# ECG_V3.net
KiCad netlist of a schematic drawn in EAGLE
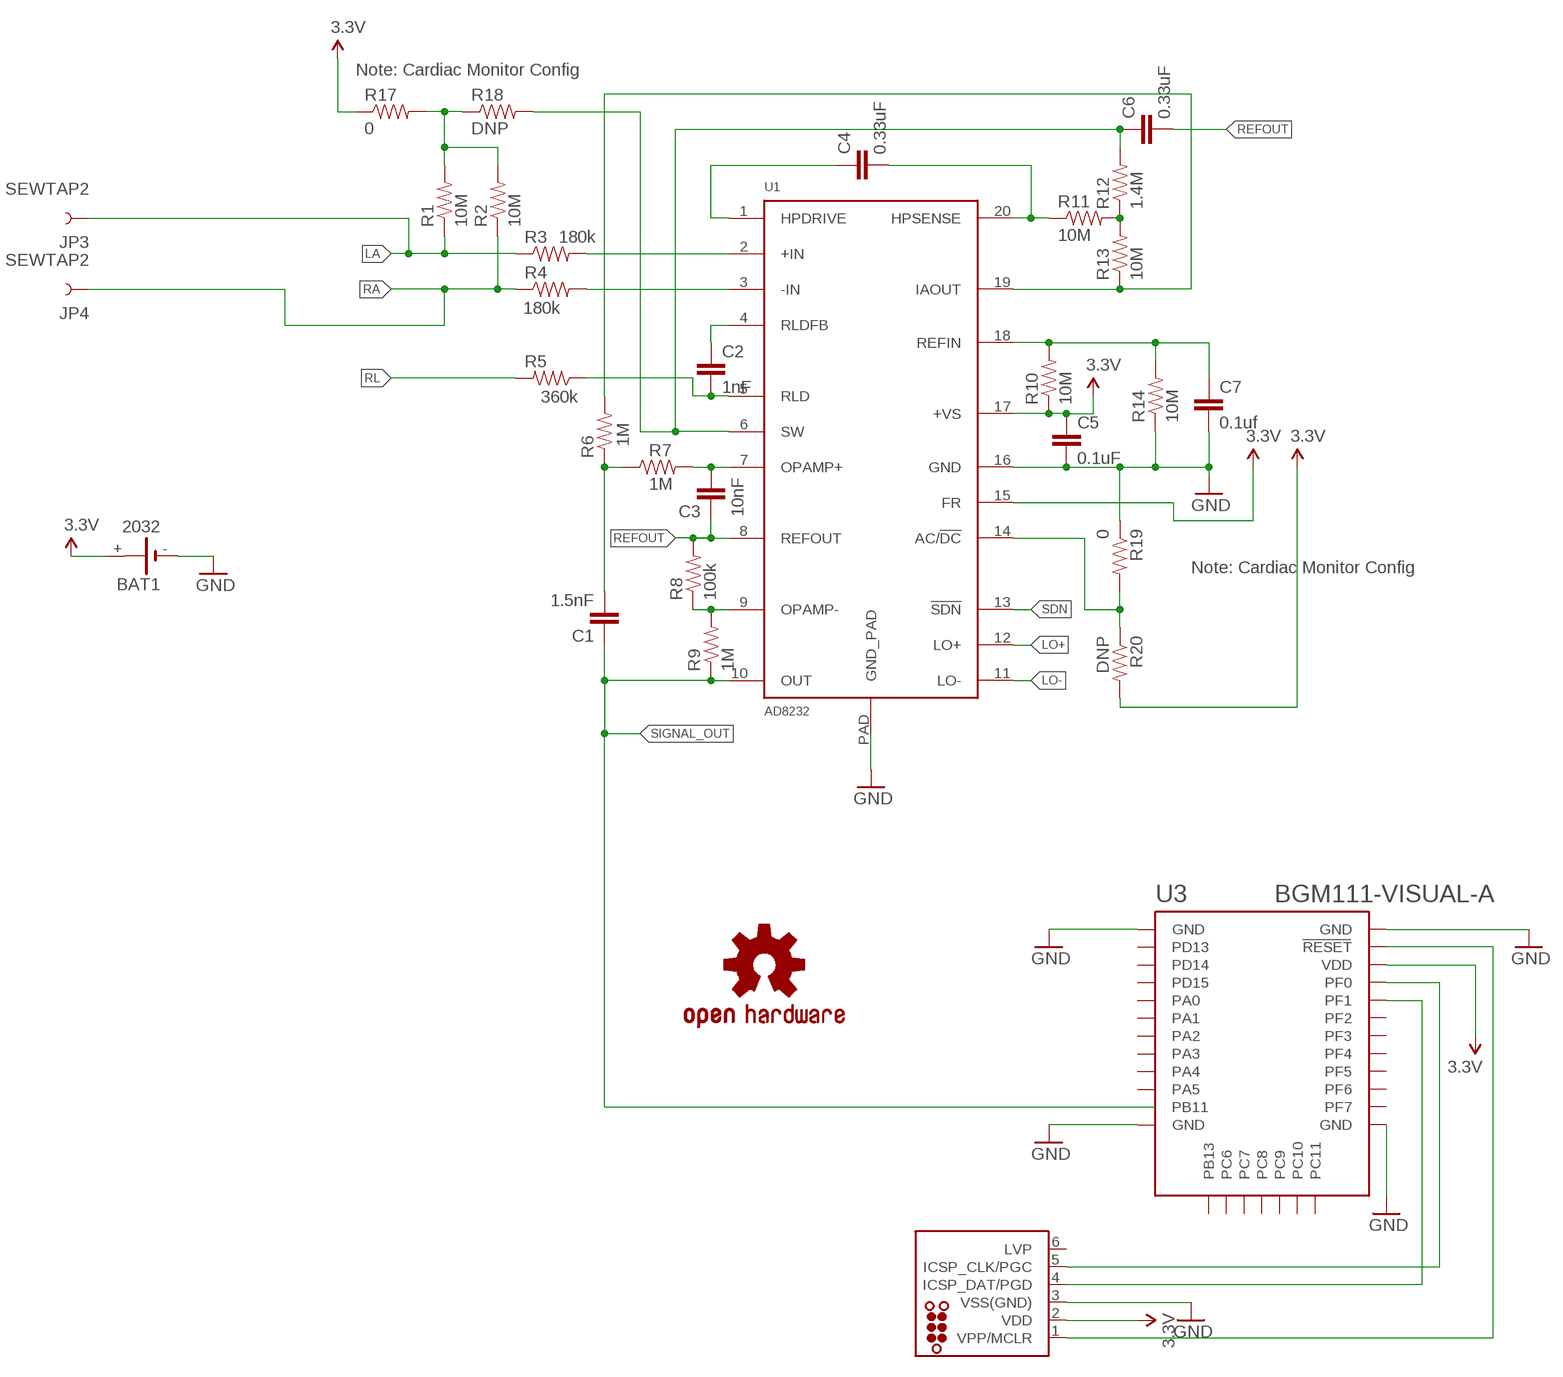
[diagram p0: schematic, sheet 1]

(export (version "E")
  (design (tool "Eeschema 10.0.6"))
  (components
    (comp (ref "BAT1")
      (value "2032")
      (footprint "eagle-import:KZH20SMD")
      (libsource (lib "eagle-import") (part "2032"))
    )
    (comp (ref "C1")
      (value "1.5nF")
      (footprint "eagle-import:0603-CAP")
      (libsource (lib "eagle-import") (part "CAP0603-CAP"))
    )
    (comp (ref "C2")
      (value "1nF")
      (footprint "eagle-import:0603-CAP")
      (libsource (lib "eagle-import") (part "CAP0603-CAP"))
    )
    (comp (ref "C3")
      (value "10nF")
      (footprint "eagle-import:0603-CAP")
      (libsource (lib "eagle-import") (part "CAP0603-CAP"))
    )
    (comp (ref "C4")
      (value "0.33uF")
      (footprint "eagle-import:0805")
      (libsource (lib "eagle-import") (part "CAP0805"))
    )
    (comp (ref "C5")
      (value "0.1uF")
      (footprint "eagle-import:0603-CAP")
      (libsource (lib "eagle-import") (part "CAP0603-CAP"))
    )
    (comp (ref "C6")
      (value "0.33uF")
      (footprint "eagle-import:0805")
      (libsource (lib "eagle-import") (part "CAP0805"))
    )
    (comp (ref "C7")
      (value "0.1uf")
      (footprint "eagle-import:0603-CAP")
      (libsource (lib "eagle-import") (part "CAP0603-CAP"))
    )
    (comp (ref "J2")
      (value "TC2030-MCP-NL")
      (footprint "eagle-import:TC2030-MCP-NL")
      (libsource (lib "eagle-import") (part "TC2030-MCP-NL"))
    )
    (comp (ref "JP3")
      (value "SEWTAP2")
      (footprint "eagle-import:PETAL-LONG-2")
      (libsource (lib "eagle-import") (part "SEWTAP2"))
    )
    (comp (ref "JP4")
      (value "SEWTAP2")
      (footprint "eagle-import:PETAL-LONG-2")
      (libsource (lib "eagle-import") (part "SEWTAP2"))
    )
    (comp (ref "LOGO1")
      (value "OSHW-LOGOS")
      (footprint "eagle-import:OSHW-LOGO-S")
      (libsource (lib "eagle-import") (part "OSHW-LOGOS"))
    )
    (comp (ref "R1")
      (value "10M")
      (footprint "eagle-import:0603-RES")
      (libsource (lib "eagle-import") (part "RESISTOR0603-RES"))
    )
    (comp (ref "R2")
      (value "10M")
      (footprint "eagle-import:0603-RES")
      (libsource (lib "eagle-import") (part "RESISTOR0603-RES"))
    )
    (comp (ref "R3")
      (value "180k")
      (footprint "eagle-import:0603-RES")
      (libsource (lib "eagle-import") (part "RESISTOR0603-RES"))
    )
    (comp (ref "R4")
      (value "180k")
      (footprint "eagle-import:0603-RES")
      (libsource (lib "eagle-import") (part "RESISTOR0603-RES"))
    )
    (comp (ref "R5")
      (value "360k")
      (footprint "eagle-import:0603-RES")
      (libsource (lib "eagle-import") (part "RESISTOR0603-RES"))
    )
    (comp (ref "R6")
      (value "1M")
      (footprint "eagle-import:0603-RES")
      (libsource (lib "eagle-import") (part "RESISTOR0603-RES"))
    )
    (comp (ref "R7")
      (value "1M")
      (footprint "eagle-import:0603-RES")
      (libsource (lib "eagle-import") (part "RESISTOR0603-RES"))
    )
    (comp (ref "R8")
      (value "100k")
      (footprint "eagle-import:0603-RES")
      (libsource (lib "eagle-import") (part "RESISTOR0603-RES"))
    )
    (comp (ref "R9")
      (value "1M")
      (footprint "eagle-import:0603-RES")
      (libsource (lib "eagle-import") (part "RESISTOR0603-RES"))
    )
    (comp (ref "R10")
      (value "10M")
      (footprint "eagle-import:0603-RES")
      (libsource (lib "eagle-import") (part "RESISTOR0603-RES"))
    )
    (comp (ref "R11")
      (value "10M")
      (footprint "eagle-import:0603-RES")
      (libsource (lib "eagle-import") (part "RESISTOR0603-RES"))
    )
    (comp (ref "R12")
      (value "1.4M")
      (footprint "eagle-import:0603-RES")
      (libsource (lib "eagle-import") (part "RESISTOR0603-RES"))
    )
    (comp (ref "R13")
      (value "10M")
      (footprint "eagle-import:0603-RES")
      (libsource (lib "eagle-import") (part "RESISTOR0603-RES"))
    )
    (comp (ref "R14")
      (value "10M")
      (footprint "eagle-import:0603-RES")
      (libsource (lib "eagle-import") (part "RESISTOR0603-RES"))
    )
    (comp (ref "R17")
      (value "0")
      (footprint "eagle-import:0603")
      (libsource (lib "eagle-import") (part "0OHM1/10W5%(0603)"))
    )
    (comp (ref "R18")
      (value "DNP")
      (footprint "eagle-import:0603")
      (libsource (lib "eagle-import") (part "0OHM1/10W5%(0603)"))
    )
    (comp (ref "R19")
      (value "0")
      (footprint "eagle-import:0603")
      (libsource (lib "eagle-import") (part "0OHM1/10W5%(0603)"))
    )
    (comp (ref "R20")
      (value "DNP")
      (footprint "eagle-import:0603")
      (libsource (lib "eagle-import") (part "0OHM1/10W5%(0603)"))
    )
    (comp (ref "U1")
      (value "AD8232")
      (footprint "eagle-import:LFCSP_20")
      (libsource (lib "eagle-import") (part "AD8232"))
    )
    (comp (ref "U3")
      (value "BGM111-VISUAL-A")
      (footprint "eagle-import:BGM111-A")
      (libsource (lib "eagle-import") (part "BGM111-VISUAL-A"))
    )
  )
  (nets
    (net (code "1") (name "3.3V") (class "Default")
      (node (ref "BAT1") (pin "+") (pinfunction "+_+") (pintype "passive"))
      (node (ref "C5") (pin "1") (pinfunction "1_1") (pintype "passive"))
      (node (ref "J2") (pin "2") (pinfunction "VDD_2") (pintype "power_in"))
      (node (ref "R10") (pin "1") (pinfunction "1_1") (pintype "passive"))
      (node (ref "R17") (pin "1") (pinfunction "1_1") (pintype "passive"))
      (node (ref "R20") (pin "2") (pinfunction "2_2") (pintype "passive"))
      (node (ref "U1") (pin "15") (pinfunction "FR_15") (pintype "bidirectional"))
      (node (ref "U1") (pin "17") (pinfunction "+VS_17") (pintype "bidirectional"))
      (node (ref "U3") (pin "VDD") (pinfunction "VDD_VDD") (pintype "power_in"))
    )
    (net (code "2") (name "GND") (class "Default")
      (node (ref "BAT1") (pin "-") (pinfunction "-_-") (pintype "passive"))
      (node (ref "C5") (pin "2") (pinfunction "2_2") (pintype "passive"))
      (node (ref "C7") (pin "2") (pinfunction "2_2") (pintype "passive"))
      (node (ref "J2") (pin "3") (pinfunction "VSS(GND)_3") (pintype "power_in"))
      (node (ref "R14") (pin "1") (pinfunction "1_1") (pintype "passive"))
      (node (ref "R19") (pin "1") (pinfunction "1_1") (pintype "passive"))
      (node (ref "U1") (pin "16") (pinfunction "GND_16") (pintype "bidirectional"))
      (node (ref "U1") (pin "PAD") (pinfunction "GND_PAD_PAD") (pintype "bidirectional"))
      (node (ref "U3") (pin "GND") (pinfunction "GND_GND") (pintype "power_in"))
      (node (ref "U3") (pin "GND@2") (pinfunction "GND_GND@2") (pintype "power_in"))
      (node (ref "U3") (pin "GND@3") (pinfunction "GND_GND@3") (pintype "power_in"))
      (node (ref "U3") (pin "GND@4") (pinfunction "GND_GND@4") (pintype "power_in"))
    )
    (net (code "3") (name "LA") (class "Default")
      (node (ref "JP3") (pin "1") (pinfunction "1_1") (pintype "bidirectional"))
      (node (ref "R1") (pin "1") (pinfunction "1_1") (pintype "passive"))
      (node (ref "R3") (pin "1") (pinfunction "1_1") (pintype "passive"))
    )
    (net (code "4") (name "LO+") (class "Default")
      (node (ref "U1") (pin "12") (pinfunction "LO+_12") (pintype "bidirectional"))
    )
    (net (code "5") (name "LO-") (class "Default")
      (node (ref "U1") (pin "11") (pinfunction "LO-_11") (pintype "bidirectional"))
    )
    (net (code "6") (name "Net-(C1-Pad2)") (class "Default")
      (node (ref "C1") (pin "2") (pinfunction "2_2") (pintype "passive"))
      (node (ref "R6") (pin "1") (pinfunction "1_1") (pintype "passive"))
      (node (ref "R7") (pin "1") (pinfunction "1_1") (pintype "passive"))
    )
    (net (code "7") (name "Net-(J2-ICSP_CLK{slash}PGC)") (class "Default")
      (node (ref "J2") (pin "5") (pinfunction "ICSP_CLK/PGC_5") (pintype "output"))
      (node (ref "U3") (pin "PF0") (pinfunction "PF0_PF0") (pintype "bidirectional"))
    )
    (net (code "8") (name "Net-(J2-ICSP_DAT{slash}PGD)") (class "Default")
      (node (ref "J2") (pin "4") (pinfunction "ICSP_DAT/PGD_4") (pintype "bidirectional"))
      (node (ref "U3") (pin "PF1") (pinfunction "PF1_PF1") (pintype "bidirectional"))
    )
    (net (code "9") (name "Net-(J2-VPP{slash}MCLR)") (class "Default")
      (node (ref "J2") (pin "1") (pinfunction "VPP/MCLR_1") (pintype "passive"))
      (node (ref "U3") (pin "RESET") (pinfunction "RESET_RESET") (pintype "input"))
    )
    (net (code "10") (name "Net-(R1-Pad2)") (class "Default")
      (node (ref "R1") (pin "2") (pinfunction "2_2") (pintype "passive"))
      (node (ref "R17") (pin "2") (pinfunction "2_2") (pintype "passive"))
      (node (ref "R18") (pin "1") (pinfunction "1_1") (pintype "passive"))
      (node (ref "R2") (pin "2") (pinfunction "2_2") (pintype "passive"))
    )
    (net (code "11") (name "Net-(R11-Pad2)") (class "Default")
      (node (ref "R11") (pin "2") (pinfunction "2_2") (pintype "passive"))
      (node (ref "R12") (pin "1") (pinfunction "1_1") (pintype "passive"))
      (node (ref "R13") (pin "2") (pinfunction "2_2") (pintype "passive"))
    )
    (net (code "12") (name "Net-(U1-+IN)") (class "Default")
      (node (ref "R3") (pin "2") (pinfunction "2_2") (pintype "passive"))
      (node (ref "U1") (pin "2") (pinfunction "+IN_2") (pintype "bidirectional"))
    )
    (net (code "13") (name "Net-(U1--IN)") (class "Default")
      (node (ref "R4") (pin "2") (pinfunction "2_2") (pintype "passive"))
      (node (ref "U1") (pin "3") (pinfunction "-IN_3") (pintype "bidirectional"))
    )
    (net (code "14") (name "Net-(U1-AC{slash}~{DC})") (class "Default")
      (node (ref "R19") (pin "2") (pinfunction "2_2") (pintype "passive"))
      (node (ref "R20") (pin "1") (pinfunction "1_1") (pintype "passive"))
      (node (ref "U1") (pin "14") (pinfunction "AC/~{DC}_14") (pintype "bidirectional"))
    )
    (net (code "15") (name "Net-(U1-HPDRIVE)") (class "Default")
      (node (ref "C4") (pin "1") (pinfunction "1_1") (pintype "passive"))
      (node (ref "U1") (pin "1") (pinfunction "HPDRIVE_1") (pintype "bidirectional"))
    )
    (net (code "16") (name "Net-(U1-HPSENSE)") (class "Default")
      (node (ref "C4") (pin "2") (pinfunction "2_2") (pintype "passive"))
      (node (ref "R11") (pin "1") (pinfunction "1_1") (pintype "passive"))
      (node (ref "U1") (pin "20") (pinfunction "HPSENSE_20") (pintype "bidirectional"))
    )
    (net (code "17") (name "Net-(U1-IAOUT)") (class "Default")
      (node (ref "R13") (pin "1") (pinfunction "1_1") (pintype "passive"))
      (node (ref "R6") (pin "2") (pinfunction "2_2") (pintype "passive"))
      (node (ref "U1") (pin "19") (pinfunction "IAOUT_19") (pintype "bidirectional"))
    )
    (net (code "18") (name "Net-(U1-OPAMP+)") (class "Default")
      (node (ref "C3") (pin "2") (pinfunction "2_2") (pintype "passive"))
      (node (ref "R7") (pin "2") (pinfunction "2_2") (pintype "passive"))
      (node (ref "U1") (pin "7") (pinfunction "OPAMP+_7") (pintype "bidirectional"))
    )
    (net (code "19") (name "Net-(U1-OPAMP-)") (class "Default")
      (node (ref "R8") (pin "1") (pinfunction "1_1") (pintype "passive"))
      (node (ref "R9") (pin "2") (pinfunction "2_2") (pintype "passive"))
      (node (ref "U1") (pin "9") (pinfunction "OPAMP-_9") (pintype "bidirectional"))
    )
    (net (code "20") (name "Net-(U1-REFIN)") (class "Default")
      (node (ref "C7") (pin "1") (pinfunction "1_1") (pintype "passive"))
      (node (ref "R10") (pin "2") (pinfunction "2_2") (pintype "passive"))
      (node (ref "R14") (pin "2") (pinfunction "2_2") (pintype "passive"))
      (node (ref "U1") (pin "18") (pinfunction "REFIN_18") (pintype "bidirectional"))
    )
    (net (code "21") (name "Net-(U1-RLD)") (class "Default")
      (node (ref "C2") (pin "2") (pinfunction "2_2") (pintype "passive"))
      (node (ref "R5") (pin "1") (pinfunction "1_1") (pintype "passive"))
      (node (ref "U1") (pin "5") (pinfunction "RLD_5") (pintype "bidirectional"))
    )
    (net (code "22") (name "Net-(U1-RLDFB)") (class "Default")
      (node (ref "C2") (pin "1") (pinfunction "1_1") (pintype "passive"))
      (node (ref "U1") (pin "4") (pinfunction "RLDFB_4") (pintype "bidirectional"))
    )
    (net (code "23") (name "Net-(U1-SW)") (class "Default")
      (node (ref "C6") (pin "1") (pinfunction "1_1") (pintype "passive"))
      (node (ref "R12") (pin "2") (pinfunction "2_2") (pintype "passive"))
      (node (ref "R18") (pin "2") (pinfunction "2_2") (pintype "passive"))
      (node (ref "U1") (pin "6") (pinfunction "SW_6") (pintype "bidirectional"))
    )
    (net (code "24") (name "RA") (class "Default")
      (node (ref "JP4") (pin "1") (pinfunction "1_1") (pintype "bidirectional"))
      (node (ref "R2") (pin "1") (pinfunction "1_1") (pintype "passive"))
      (node (ref "R4") (pin "1") (pinfunction "1_1") (pintype "passive"))
    )
    (net (code "25") (name "REFOUT") (class "Default")
      (node (ref "C3") (pin "1") (pinfunction "1_1") (pintype "passive"))
      (node (ref "C6") (pin "2") (pinfunction "2_2") (pintype "passive"))
      (node (ref "R8") (pin "2") (pinfunction "2_2") (pintype "passive"))
      (node (ref "U1") (pin "8") (pinfunction "REFOUT_8") (pintype "bidirectional"))
    )
    (net (code "26") (name "RL") (class "Default")
      (node (ref "R5") (pin "2") (pinfunction "2_2") (pintype "passive"))
    )
    (net (code "27") (name "SDN") (class "Default")
      (node (ref "U1") (pin "13") (pinfunction "~{SDN}_13") (pintype "bidirectional"))
    )
    (net (code "28") (name "SIGNAL_OUT") (class "Default")
      (node (ref "C1") (pin "1") (pinfunction "1_1") (pintype "passive"))
      (node (ref "R9") (pin "1") (pinfunction "1_1") (pintype "passive"))
      (node (ref "U1") (pin "10") (pinfunction "OUT_10") (pintype "bidirectional"))
    )
    (net (code "29") (name "unconnected-(J2-LVP-Pad6)") (class "Default")
      (node (ref "J2") (pin "6") (pinfunction "LVP_6") (pintype "bidirectional"))
    )
    (net (code "30") (name "unconnected-(U3-PadPA0)") (class "Default")
      (node (ref "U3") (pin "PA0") (pinfunction "PA0_PA0") (pintype "bidirectional"))
    )
    (net (code "31") (name "unconnected-(U3-PadPA1)") (class "Default")
      (node (ref "U3") (pin "PA1") (pinfunction "PA1_PA1") (pintype "bidirectional"))
    )
    (net (code "32") (name "unconnected-(U3-PadPA2)") (class "Default")
      (node (ref "U3") (pin "PA2") (pinfunction "PA2_PA2") (pintype "bidirectional"))
    )
    (net (code "33") (name "unconnected-(U3-PadPA3)") (class "Default")
      (node (ref "U3") (pin "PA3") (pinfunction "PA3_PA3") (pintype "bidirectional"))
    )
    (net (code "34") (name "unconnected-(U3-PadPA4)") (class "Default")
      (node (ref "U3") (pin "PA4") (pinfunction "PA4_PA4") (pintype "bidirectional"))
    )
    (net (code "35") (name "unconnected-(U3-PadPA5)") (class "Default")
      (node (ref "U3") (pin "PA5") (pinfunction "PA5_PA5") (pintype "bidirectional"))
    )
    (net (code "36") (name "unconnected-(U3-PadPB11)") (class "Default")
      (node (ref "U3") (pin "PB11") (pinfunction "PB11_PB11") (pintype "bidirectional"))
    )
    (net (code "37") (name "unconnected-(U3-PadPB13)") (class "Default")
      (node (ref "U3") (pin "PB13") (pinfunction "PB13_PB13") (pintype "bidirectional"))
    )
    (net (code "38") (name "unconnected-(U3-PadPC6)") (class "Default")
      (node (ref "U3") (pin "PC6") (pinfunction "PC6_PC6") (pintype "bidirectional"))
    )
    (net (code "39") (name "unconnected-(U3-PadPC7)") (class "Default")
      (node (ref "U3") (pin "PC7") (pinfunction "PC7_PC7") (pintype "bidirectional"))
    )
    (net (code "40") (name "unconnected-(U3-PadPC8)") (class "Default")
      (node (ref "U3") (pin "PC8") (pinfunction "PC8_PC8") (pintype "bidirectional"))
    )
    (net (code "41") (name "unconnected-(U3-PadPC9)") (class "Default")
      (node (ref "U3") (pin "PC9") (pinfunction "PC9_PC9") (pintype "bidirectional"))
    )
    (net (code "42") (name "unconnected-(U3-PadPC10)") (class "Default")
      (node (ref "U3") (pin "PC10") (pinfunction "PC10_PC10") (pintype "bidirectional"))
    )
    (net (code "43") (name "unconnected-(U3-PadPC11)") (class "Default")
      (node (ref "U3") (pin "PC11") (pinfunction "PC11_PC11") (pintype "bidirectional"))
    )
    (net (code "44") (name "unconnected-(U3-PadPD13)") (class "Default")
      (node (ref "U3") (pin "PD13") (pinfunction "PD13_PD13") (pintype "bidirectional"))
    )
    (net (code "45") (name "unconnected-(U3-PadPD14)") (class "Default")
      (node (ref "U3") (pin "PD14") (pinfunction "PD14_PD14") (pintype "bidirectional"))
    )
    (net (code "46") (name "unconnected-(U3-PadPD15)") (class "Default")
      (node (ref "U3") (pin "PD15") (pinfunction "PD15_PD15") (pintype "bidirectional"))
    )
    (net (code "47") (name "unconnected-(U3-PadPF2)") (class "Default")
      (node (ref "U3") (pin "PF2") (pinfunction "PF2_PF2") (pintype "bidirectional"))
    )
    (net (code "48") (name "unconnected-(U3-PadPF3)") (class "Default")
      (node (ref "U3") (pin "PF3") (pinfunction "PF3_PF3") (pintype "bidirectional"))
    )
    (net (code "49") (name "unconnected-(U3-PadPF4)") (class "Default")
      (node (ref "U3") (pin "PF4") (pinfunction "PF4_PF4") (pintype "bidirectional"))
    )
    (net (code "50") (name "unconnected-(U3-PadPF5)") (class "Default")
      (node (ref "U3") (pin "PF5") (pinfunction "PF5_PF5") (pintype "bidirectional"))
    )
    (net (code "51") (name "unconnected-(U3-PadPF6)") (class "Default")
      (node (ref "U3") (pin "PF6") (pinfunction "PF6_PF6") (pintype "bidirectional"))
    )
    (net (code "52") (name "unconnected-(U3-PadPF7)") (class "Default")
      (node (ref "U3") (pin "PF7") (pinfunction "PF7_PF7") (pintype "bidirectional"))
    )
  )
)
